# ST_LINK_V2.net
KiCad netlist of a schematic drawn in Altium Designer
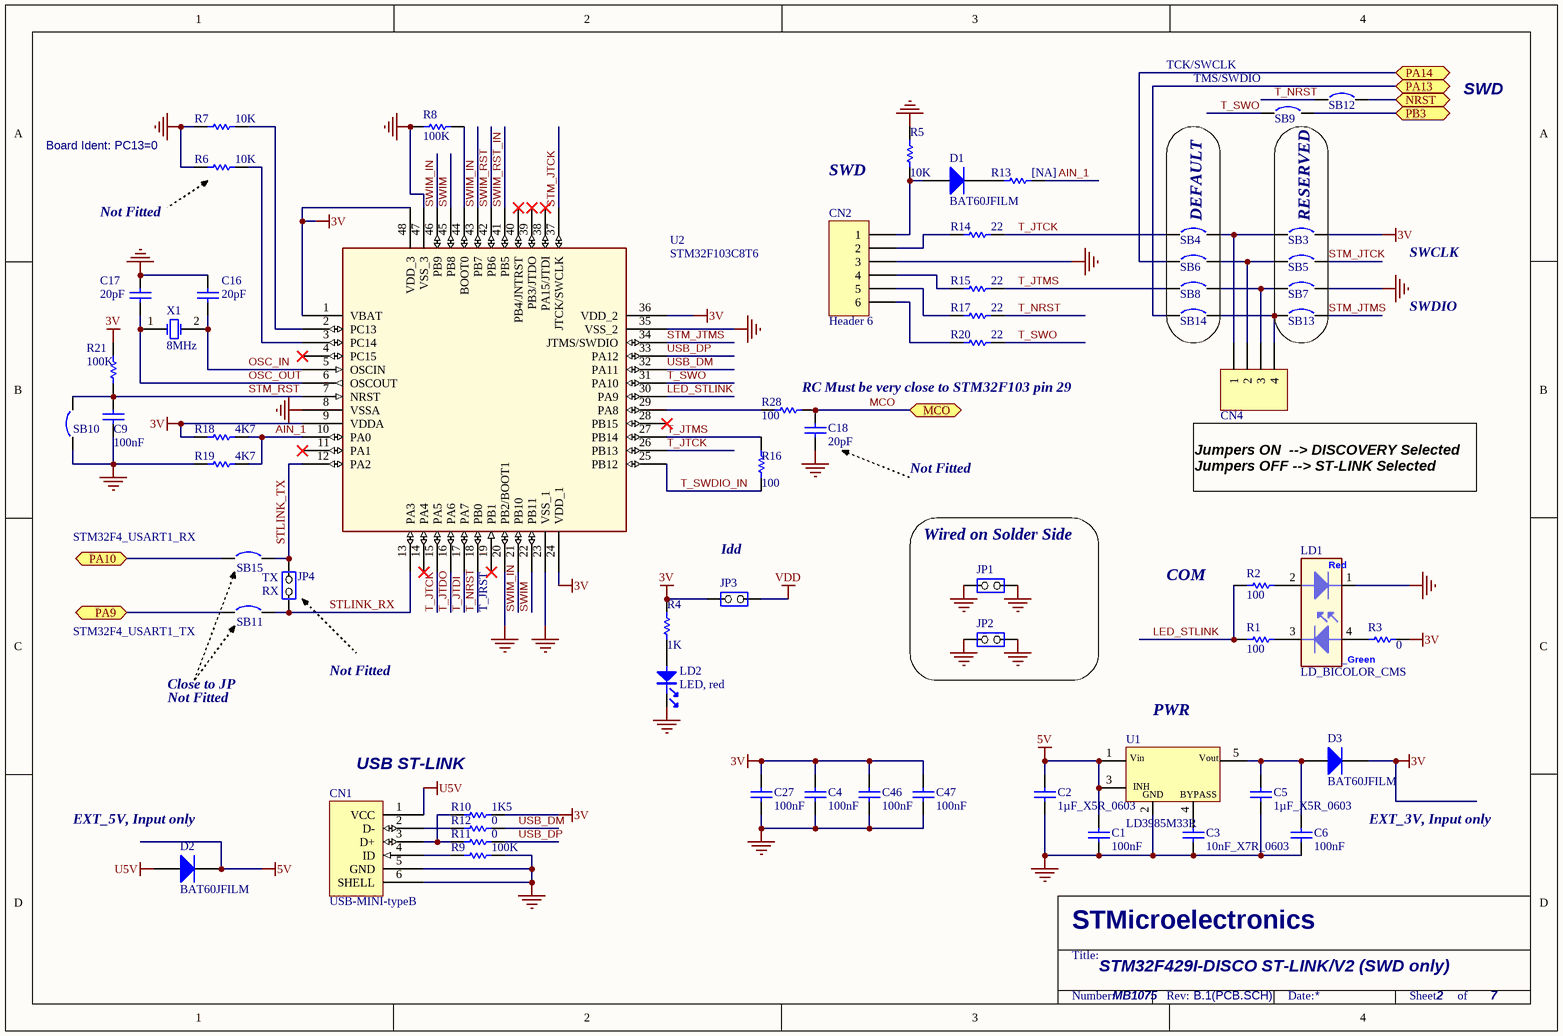
[diagram p0: ST_LINK_V2.SCHDOC]

(export (version "E")
  (design (tool "Eeschema 10.0.6"))
  (components
    (comp (ref "C1")
      (value "100nF")
      (footprint "0402C")
      (description "Capacitor 0402 / 0603 / 0805")
      (libsource (lib "MCD_TOOLS") (part "Capacitor_ST"))
    )
    (comp (ref "C2")
      (value "1µF_X5R_0603")
      (footprint "0603C")
      (description "0603  X5R 1µF")
      (fields (field (name "TOLERANCE") "10%"))
      (libsource (lib "MB963_1") (part "CAP SMD 0603  X5R 1µF 25V 10%"))
    )
    (comp (ref "C3")
      (value "10nF_X7R_0603")
      (footprint "0603C")
      (description "0603  X7R 10NF")
      (fields (field (name "TOLERANCE") "10%"))
      (libsource (lib "MB963_1") (part "CAP SMD 0603  X7R 10000PF 50V 10%"))
    )
    (comp (ref "C4")
      (value "100nF")
      (footprint "0402C")
      (description "Capacitor 0402 / 0603 / 0805")
      (libsource (lib "MCD_TOOLS") (part "Capacitor_ST"))
    )
    (comp (ref "C5")
      (value "1µF_X5R_0603")
      (footprint "0603C")
      (description "0603  X5R 1µF")
      (fields (field (name "TOLERANCE") "10%"))
      (libsource (lib "MB963_1") (part "CAP SMD 0603  X5R 1µF 25V 10%"))
    )
    (comp (ref "C6")
      (value "100nF")
      (footprint "0402C")
      (description "Capacitor 0402 / 0603 / 0805")
      (libsource (lib "MCD_TOOLS") (part "Capacitor_ST"))
    )
    (comp (ref "C9")
      (value "100nF")
      (footprint "0402C")
      (description "Capacitor 0402 / 0603 / 0805")
      (libsource (lib "MCD_TOOLS") (part "Capacitor_ST"))
    )
    (comp (ref "C16")
      (value "20pF")
      (footprint "0402C")
      (description "Capacitor 0402 / 0603 / 0805")
      (libsource (lib "MCD_TOOLS") (part "Capacitor_ST"))
    )
    (comp (ref "C17")
      (value "20pF")
      (footprint "0402C")
      (description "Capacitor 0402 / 0603 / 0805")
      (libsource (lib "MCD_TOOLS") (part "Capacitor_ST"))
    )
    (comp (ref "C18")
      (value "20pF")
      (footprint "0402C")
      (description "Capacitor 0402 / 0603 / 0805")
      (libsource (lib "MCD_TOOLS") (part "Capacitor_ST"))
    )
    (comp (ref "C27")
      (value "100nF")
      (footprint "0402C")
      (description "Capacitor 0402 / 0603 / 0805")
      (libsource (lib "MCD_TOOLS") (part "Capacitor_ST"))
    )
    (comp (ref "C46")
      (value "100nF")
      (footprint "0402C")
      (description "Capacitor 0402 / 0603 / 0805")
      (libsource (lib "MCD_TOOLS") (part "Capacitor_ST"))
    )
    (comp (ref "C47")
      (value "100nF")
      (footprint "0402C")
      (description "Capacitor 0402 / 0603 / 0805")
      (libsource (lib "MCD_TOOLS") (part "Capacitor_ST"))
    )
    (comp (ref "CN1")
      (value "USB-MINI-typeB")
      (footprint "STM-SMEE:USB-MINI-B-SMD")
      (description "USB,MINI-USB-5P/F, 5075BMR-05-M")
      (libsource (lib "MCD_TOOLS") (part "USB-MINI-typeB connector"))
    )
    (comp (ref "CN2")
      (value "Header 6")
      (footprint "HDR1X6")
      (description "Header, 6-Pin")
      (fields (field (name "PUBLISHER") "Altium Limited"))
      (libsource (lib "Miscellaneous Connectors") (part "Header 6"))
    )
    (comp (ref "CN4")
      (value "Header 4")
      (footprint "Header 4")
      (description "Header, 4-Pin")
      (fields (field (name "PUBLISHER") "Altium Limited"))
      (libsource (lib "MB963_1") (part "Header 4"))
    )
    (comp (ref "D1")
      (value "BAT60JFILM")
      (footprint "SOD323/A")
      (libsource (lib "MCD_TOOLS") (part "BAT60JFILM"))
    )
    (comp (ref "D2")
      (value "BAT60JFILM")
      (footprint "SOD323/A")
      (libsource (lib "MCD_TOOLS") (part "BAT60JFILM"))
    )
    (comp (ref "D3")
      (value "BAT60JFILM")
      (footprint "SOD323/A")
      (libsource (lib "MCD_TOOLS") (part "BAT60JFILM"))
    )
    (comp (ref "JP1") (value "~") (footprint "SIP2/2.54") (libsource (lib "*") (part "JP2")))
    (comp (ref "JP2") (value "~") (footprint "SIP2/2.54") (libsource (lib "*") (part "JP2")))
    (comp (ref "JP3") (value "~") (footprint "SIP2/2.54") (libsource (lib "*") (part "JP2")))
    (comp (ref "JP4") (value "JP2") (footprint "SIP2/2.54") (libsource (lib "MCD_TOOLS") (part "JP2")))
    (comp (ref "LD1")
      (value "LD_BICOLOR_CMS")
      (footprint "STM-SMEE:HSMF-A201")
      (description "Bicolor Led")
      (libsource (lib "MCD_TOOLS") (part "LD_BICOLOR_CMS"))
    )
    (comp (ref "LD2")
      (value "LED, red")
      (footprint "0603D")
      (description "LED,red,0603,19-213-R6C-AP1Q2B/3T,everlight")
      (libsource (lib "MCD_TOOLS") (part "LED_red"))
    )
    (comp (ref "R1")
      (value "100")
      (footprint "0402R")
      (description "Resistor 0402 or 0603 or 0805")
      (libsource (lib "MCD_TOOLS") (part "Resistor_ST"))
    )
    (comp (ref "R2")
      (value "100")
      (footprint "0402R")
      (description "Resistor 0402 or 0603 or 0805")
      (libsource (lib "MCD_TOOLS") (part "Resistor_ST"))
    )
    (comp (ref "R3")
      (value "0")
      (footprint "0402R")
      (description "Resistor 0402 or 0603 or 0805")
      (libsource (lib "MCD_TOOLS") (part "Resistor_ST"))
    )
    (comp (ref "R4")
      (value "1K")
      (footprint "0402R")
      (description "Resistor 0402 or 0603 or 0805")
      (libsource (lib "MCD_TOOLS") (part "Resistor_ST"))
    )
    (comp (ref "R5")
      (value "10K")
      (footprint "0402R")
      (description "Resistor 0402 or 0603 or 0805")
      (libsource (lib "MCD_TOOLS") (part "Resistor_ST"))
    )
    (comp (ref "R6")
      (value "10K")
      (footprint "0402R")
      (description "Resistor 0402 or 0603 or 0805")
      (libsource (lib "MCD_TOOLS") (part "Resistor_ST"))
    )
    (comp (ref "R7")
      (value "10K")
      (footprint "0402R")
      (description "Resistor 0402 or 0603 or 0805")
      (libsource (lib "MCD_TOOLS") (part "Resistor_ST"))
    )
    (comp (ref "R8")
      (value "100K")
      (footprint "0402R")
      (description "Resistor 0402 or 0603 or 0805")
      (libsource (lib "MCD_TOOLS") (part "Resistor_ST"))
    )
    (comp (ref "R9")
      (value "100K")
      (footprint "0402R")
      (description "Resistor 0402 or 0603 or 0805")
      (libsource (lib "MCD_TOOLS") (part "Resistor_ST"))
    )
    (comp (ref "R10")
      (value "1K5")
      (footprint "0402R")
      (description "Resistor 0402 or 0603 or 0805")
      (libsource (lib "MCD_TOOLS") (part "Resistor_ST"))
    )
    (comp (ref "R11")
      (value "0")
      (footprint "0402R")
      (description "Resistor 0402 or 0603 or 0805")
      (libsource (lib "MCD_TOOLS") (part "Resistor_ST"))
    )
    (comp (ref "R12")
      (value "0")
      (footprint "0402R")
      (description "Resistor 0402 or 0603 or 0805")
      (libsource (lib "MCD_TOOLS") (part "Resistor_ST"))
    )
    (comp (ref "R13")
      (value "[NA]")
      (footprint "0402R")
      (description "Resistor 0402 or 0603 or 0805")
      (libsource (lib "MCD_TOOLS") (part "Resistor_ST"))
    )
    (comp (ref "R14")
      (value "22")
      (footprint "0402R")
      (description "Resistor 0402 or 0603 or 0805")
      (libsource (lib "MCD_TOOLS") (part "Resistor_ST"))
    )
    (comp (ref "R15")
      (value "22")
      (footprint "0402R")
      (description "Resistor 0402 or 0603 or 0805")
      (libsource (lib "MCD_TOOLS") (part "Resistor_ST"))
    )
    (comp (ref "R16")
      (value "100")
      (footprint "0402R")
      (description "Resistor 0402 or 0603 or 0805")
      (libsource (lib "MCD_TOOLS") (part "Resistor_ST"))
    )
    (comp (ref "R17")
      (value "22")
      (footprint "0402R")
      (description "Resistor 0402 or 0603 or 0805")
      (libsource (lib "MCD_TOOLS") (part "Resistor_ST"))
    )
    (comp (ref "R18")
      (value "4K7")
      (footprint "0402R")
      (description "Resistor 0402 or 0603 or 0805")
      (libsource (lib "MCD_TOOLS") (part "Resistor_ST"))
    )
    (comp (ref "R19")
      (value "4K7")
      (footprint "0402R")
      (description "Resistor 0402 or 0603 or 0805")
      (libsource (lib "MCD_TOOLS") (part "Resistor_ST"))
    )
    (comp (ref "R20")
      (value "22")
      (footprint "0402R")
      (description "Resistor 0402 or 0603 or 0805")
      (libsource (lib "MCD_TOOLS") (part "Resistor_ST"))
    )
    (comp (ref "R21")
      (value "100K")
      (footprint "0402R")
      (description "Resistor 0402 or 0603 or 0805")
      (libsource (lib "MCD_TOOLS") (part "Resistor_ST"))
    )
    (comp (ref "R28")
      (value "100")
      (footprint "0402R")
      (description "Resistor 0402 or 0603 or 0805")
      (libsource (lib "MCD_TOOLS") (part "Resistor_ST"))
    )
    (comp (ref "SB3")
      (value "Circuit Breaker")
      (footprint "JP2_SMD")
      (fields (field (name "PUBLISHER") "Altium Limited"))
      (libsource (lib "MB915") (part "Circuit Breaker"))
    )
    (comp (ref "SB4")
      (value "Circuit Breaker")
      (footprint "JP2_SMD")
      (fields (field (name "PUBLISHER") "Altium Limited"))
      (libsource (lib "MB915") (part "Circuit Breaker"))
    )
    (comp (ref "SB5")
      (value "Circuit Breaker")
      (footprint "JP2_SMD")
      (fields (field (name "PUBLISHER") "Altium Limited"))
      (libsource (lib "MB915") (part "Circuit Breaker"))
    )
    (comp (ref "SB6")
      (value "Circuit Breaker")
      (footprint "JP2_SMD")
      (fields (field (name "PUBLISHER") "Altium Limited"))
      (libsource (lib "MB915") (part "Circuit Breaker"))
    )
    (comp (ref "SB7")
      (value "Circuit Breaker")
      (footprint "JP2_SMD")
      (fields (field (name "PUBLISHER") "Altium Limited"))
      (libsource (lib "MB915") (part "Circuit Breaker"))
    )
    (comp (ref "SB8")
      (value "Circuit Breaker")
      (footprint "JP2_SMD")
      (fields (field (name "PUBLISHER") "Altium Limited"))
      (libsource (lib "MB915") (part "Circuit Breaker"))
    )
    (comp (ref "SB9")
      (value "Circuit Breaker")
      (footprint "JP2_SMD")
      (fields (field (name "PUBLISHER") "Altium Limited"))
      (libsource (lib "MCD_TOOLS") (part "Circuit Breaker"))
    )
    (comp (ref "SB10")
      (value "Circuit Breaker")
      (footprint "JP2_SMD")
      (fields (field (name "PUBLISHER") "Altium Limited"))
      (libsource (lib "MB915") (part "Circuit Breaker"))
    )
    (comp (ref "SB11")
      (value "Circuit Breaker")
      (footprint "JP2_SMD")
      (fields (field (name "PUBLISHER") "Altium Limited"))
      (libsource (lib "MCD_TOOLS") (part "Circuit Breaker"))
    )
    (comp (ref "SB12")
      (value "Circuit Breaker")
      (footprint "JP2_SMD")
      (fields (field (name "PUBLISHER") "Altium Limited"))
      (libsource (lib "MB915") (part "Circuit Breaker"))
    )
    (comp (ref "SB13")
      (value "Circuit Breaker")
      (footprint "JP2_SMD")
      (fields (field (name "PUBLISHER") "Altium Limited"))
      (libsource (lib "MB915") (part "Circuit Breaker"))
    )
    (comp (ref "SB14")
      (value "Circuit Breaker")
      (footprint "JP2_SMD")
      (fields (field (name "PUBLISHER") "Altium Limited"))
      (libsource (lib "MB915") (part "Circuit Breaker"))
    )
    (comp (ref "SB15")
      (value "Circuit Breaker")
      (footprint "JP2_SMD")
      (fields (field (name "PUBLISHER") "Altium Limited"))
      (libsource (lib "MCD_TOOLS") (part "Circuit Breaker"))
    )
    (comp (ref "U1")
      (value "LD3985M33R")
      (footprint "STM-SMEE:SOT-23-5L")
      (description "Ultra low drop-low noise BiCMOS voltage, regulators low ESR capacitors compatible")
      (libsource (lib "MCD_TOOLS") (part "LD3985M33R"))
    )
    (comp (ref "U2")
      (value "STM32F103C8T6")
      (footprint "QFP48 7X7")
      (description "Medium-density performance line ARM-based 32-bit MCU with 64KB Flash")
      (libsource (lib "MCD_TOOLS") (part "STM32F103C8T6"))
    )
    (comp (ref "X1")
      (value "8MHz")
      (footprint "STM-SMEE:XTAL1")
      (description "Crystal Oscillator,8Mhz,20PF,20PPM,-10-70 degree,DIP,HC-49S")
      (libsource (lib "MCD_TOOLS") (part "XTAL"))
    )
  )
  (nets
    (net (code "1") (name "/AIN_1") (class "Default")
      (node (ref "R13") (pin "2") (pinfunction "2_2") (pintype "passive"))
      (node (ref "R18") (pin "2") (pinfunction "2_2") (pintype "passive"))
      (node (ref "R19") (pin "2") (pinfunction "2_2") (pintype "passive"))
      (node (ref "U2") (pin "10") (pinfunction "PA0_10") (pintype "bidirectional"))
    )
    (net (code "2") (name "/LED_STLINK") (class "Default")
      (node (ref "R1") (pin "1") (pinfunction "1_1") (pintype "passive"))
      (node (ref "R2") (pin "1") (pinfunction "1_1") (pintype "passive"))
      (node (ref "U2") (pin "30") (pinfunction "PA9_30") (pintype "bidirectional"))
    )
    (net (code "3") (name "/MCO") (class "Default")
      (node (ref "C18") (pin "2") (pinfunction "2_2") (pintype "passive"))
      (node (ref "R28") (pin "2") (pinfunction "2_2") (pintype "passive"))
    )
    (net (code "4") (name "/NRST") (class "Default")
      (node (ref "SB12") (pin "2") (pinfunction "2_2") (pintype "passive"))
    )
    (net (code "5") (name "/OSC_IN") (class "Default")
      (node (ref "C16") (pin "1") (pinfunction "1_1") (pintype "passive"))
      (node (ref "U2") (pin "5") (pinfunction "OSCIN_5") (pintype "input"))
      (node (ref "X1") (pin "2") (pinfunction "OSC2_2") (pintype "passive"))
    )
    (net (code "6") (name "/OSC_OUT") (class "Default")
      (node (ref "C17") (pin "1") (pinfunction "1_1") (pintype "passive"))
      (node (ref "U2") (pin "6") (pinfunction "OSCOUT_6") (pintype "output"))
      (node (ref "X1") (pin "1") (pinfunction "OSC1_1") (pintype "passive"))
    )
    (net (code "7") (name "/PA9") (class "Default")
      (node (ref "SB11") (pin "1") (pinfunction "1_1") (pintype "passive"))
    )
    (net (code "8") (name "/PA10") (class "Default")
      (node (ref "SB15") (pin "1") (pinfunction "1_1") (pintype "passive"))
    )
    (net (code "9") (name "/PA13") (class "Default")
      (node (ref "SB14") (pin "1") (pinfunction "1_1") (pintype "passive"))
    )
    (net (code "10") (name "/PA14") (class "Default")
      (node (ref "SB6") (pin "1") (pinfunction "1_1") (pintype "passive"))
    )
    (net (code "11") (name "/PB3") (class "Default")
      (node (ref "SB9") (pin "2") (pinfunction "2_2") (pintype "passive"))
    )
    (net (code "12") (name "/STLINK_RX") (class "Default")
      (node (ref "JP4") (pin "1") (pinfunction "COMMON_1") (pintype "passive"))
      (node (ref "SB11") (pin "2") (pinfunction "2_2") (pintype "passive"))
      (node (ref "U2") (pin "13") (pinfunction "PA3_13") (pintype "bidirectional"))
    )
    (net (code "13") (name "/STLINK_TX") (class "Default")
      (node (ref "JP4") (pin "2") (pinfunction "NO_2") (pintype "passive"))
      (node (ref "SB15") (pin "2") (pinfunction "2_2") (pintype "passive"))
      (node (ref "U2") (pin "12") (pinfunction "PA2_12") (pintype "bidirectional"))
    )
    (net (code "14") (name "/STM_JTCK") (class "Default")
      (node (ref "SB5") (pin "2") (pinfunction "2_2") (pintype "passive"))
      (node (ref "U2") (pin "37") (pinfunction "JTCK/SWCLK_37") (pintype "bidirectional"))
    )
    (net (code "15") (name "/STM_JTMS") (class "Default")
      (node (ref "SB13") (pin "2") (pinfunction "2_2") (pintype "passive"))
      (node (ref "U2") (pin "34") (pinfunction "JTMS/SWDIO_34") (pintype "bidirectional"))
    )
    (net (code "16") (name "/STM_RST") (class "Default")
      (node (ref "C9") (pin "2") (pinfunction "2_2") (pintype "passive"))
      (node (ref "R21") (pin "1") (pinfunction "1_1") (pintype "passive"))
      (node (ref "SB10") (pin "2") (pinfunction "2_2") (pintype "passive"))
      (node (ref "U2") (pin "7") (pinfunction "NRST_7") (pintype "input"))
    )
    (net (code "17") (name "/SWIM") (class "Default")
      (node (ref "U2") (pin "22") (pinfunction "PB11_22") (pintype "bidirectional"))
      (node (ref "U2") (pin "45") (pinfunction "PB8_45") (pintype "bidirectional"))
    )
    (net (code "18") (name "/SWIM_IN") (class "Default")
      (node (ref "U2") (pin "21") (pinfunction "PB10_21") (pintype "bidirectional"))
      (node (ref "U2") (pin "43") (pinfunction "PB7_43") (pintype "bidirectional"))
      (node (ref "U2") (pin "46") (pinfunction "PB9_46") (pintype "bidirectional"))
    )
    (net (code "19") (name "/SWIM_RST") (class "Default")
      (node (ref "U2") (pin "42") (pinfunction "PB6_42") (pintype "bidirectional"))
    )
    (net (code "20") (name "/SWIM_RST_IN") (class "Default")
      (node (ref "U2") (pin "41") (pinfunction "PB5_41") (pintype "bidirectional"))
    )
    (net (code "21") (name "/T_JTCK") (class "Default")
      (node (ref "R14") (pin "2") (pinfunction "2_2") (pintype "passive"))
      (node (ref "SB4") (pin "1") (pinfunction "1_1") (pintype "passive"))
      (node (ref "U2") (pin "15") (pinfunction "PA5_15") (pintype "bidirectional"))
      (node (ref "U2") (pin "26") (pinfunction "PB13_26") (pintype "bidirectional"))
    )
    (net (code "22") (name "/T_JTDI") (class "Default")
      (node (ref "U2") (pin "17") (pinfunction "PA7_17") (pintype "bidirectional"))
    )
    (net (code "23") (name "/T_JTDO") (class "Default")
      (node (ref "U2") (pin "16") (pinfunction "PA6_16") (pintype "bidirectional"))
    )
    (net (code "24") (name "/T_JTMS") (class "Default")
      (node (ref "R15") (pin "2") (pinfunction "2_2") (pintype "passive"))
      (node (ref "R16") (pin "2") (pinfunction "2_2") (pintype "passive"))
      (node (ref "SB8") (pin "1") (pinfunction "1_1") (pintype "passive"))
      (node (ref "U2") (pin "27") (pinfunction "PB14_27") (pintype "bidirectional"))
    )
    (net (code "25") (name "/T_NRST") (class "Default")
      (node (ref "R17") (pin "2") (pinfunction "2_2") (pintype "passive"))
      (node (ref "SB12") (pin "1") (pinfunction "1_1") (pintype "passive"))
      (node (ref "U2") (pin "18") (pinfunction "PB0_18") (pintype "bidirectional"))
    )
    (net (code "26") (name "/T_SWDIO_IN") (class "Default")
      (node (ref "R16") (pin "1") (pinfunction "1_1") (pintype "passive"))
      (node (ref "U2") (pin "25") (pinfunction "PB12_25") (pintype "bidirectional"))
    )
    (net (code "27") (name "/T_SWO") (class "Default")
      (node (ref "R20") (pin "2") (pinfunction "2_2") (pintype "passive"))
      (node (ref "SB9") (pin "1") (pinfunction "1_1") (pintype "passive"))
      (node (ref "U2") (pin "31") (pinfunction "PA10_31") (pintype "bidirectional"))
    )
    (net (code "28") (name "/USB_DM") (class "Default")
      (node (ref "R12") (pin "2") (pinfunction "2_2") (pintype "passive"))
      (node (ref "U2") (pin "32") (pinfunction "PA11_32") (pintype "bidirectional"))
    )
    (net (code "29") (name "/USB_DP") (class "Default")
      (node (ref "R11") (pin "2") (pinfunction "2_2") (pintype "passive"))
      (node (ref "U2") (pin "33") (pinfunction "PA12_33") (pintype "bidirectional"))
    )
    (net (code "30") (name "3V") (class "Default")
      (node (ref "C27") (pin "2") (pinfunction "2_2") (pintype "passive"))
      (node (ref "C4") (pin "2") (pinfunction "2_2") (pintype "passive"))
      (node (ref "C46") (pin "2") (pinfunction "2_2") (pintype "passive"))
      (node (ref "C47") (pin "2") (pinfunction "2_2") (pintype "passive"))
      (node (ref "D3") (pin "2") (pinfunction "K_2") (pintype "passive"))
      (node (ref "JP3") (pin "1") (pinfunction "COMMON_1") (pintype "passive"))
      (node (ref "R10") (pin "2") (pinfunction "2_2") (pintype "passive"))
      (node (ref "R18") (pin "1") (pinfunction "1_1") (pintype "passive"))
      (node (ref "R21") (pin "2") (pinfunction "2_2") (pintype "passive"))
      (node (ref "R3") (pin "2") (pinfunction "2_2") (pintype "passive"))
      (node (ref "R4") (pin "2") (pinfunction "2_2") (pintype "passive"))
      (node (ref "SB3") (pin "2") (pinfunction "2_2") (pintype "passive"))
      (node (ref "U2") (pin "1") (pinfunction "VBAT_1") (pintype "power_in"))
      (node (ref "U2") (pin "24") (pinfunction "VDD_1_24") (pintype "power_in"))
      (node (ref "U2") (pin "36") (pinfunction "VDD_2_36") (pintype "power_in"))
      (node (ref "U2") (pin "48") (pinfunction "VDD_3_48") (pintype "power_in"))
      (node (ref "U2") (pin "9") (pinfunction "VDDA_9") (pintype "power_in"))
    )
    (net (code "31") (name "5V") (class "Default")
      (node (ref "C1") (pin "2") (pinfunction "2_2") (pintype "passive"))
      (node (ref "C2") (pin "2") (pinfunction "2_2") (pintype "passive"))
      (node (ref "D2") (pin "2") (pinfunction "K_2") (pintype "passive"))
      (node (ref "U1") (pin "1") (pinfunction "Vin_1") (pintype "passive"))
      (node (ref "U1") (pin "3") (pinfunction "CE_3") (pintype "passive"))
    )
    (net (code "32") (name "GND") (class "Default")
      (node (ref "C1") (pin "1") (pinfunction "1_1") (pintype "passive"))
      (node (ref "C16") (pin "2") (pinfunction "2_2") (pintype "passive"))
      (node (ref "C17") (pin "2") (pinfunction "2_2") (pintype "passive"))
      (node (ref "C18") (pin "1") (pinfunction "1_1") (pintype "passive"))
      (node (ref "C2") (pin "1") (pinfunction "1_1") (pintype "passive"))
      (node (ref "C27") (pin "1") (pinfunction "1_1") (pintype "passive"))
      (node (ref "C3") (pin "1") (pinfunction "1_1") (pintype "passive"))
      (node (ref "C4") (pin "1") (pinfunction "1_1") (pintype "passive"))
      (node (ref "C46") (pin "1") (pinfunction "1_1") (pintype "passive"))
      (node (ref "C47") (pin "1") (pinfunction "1_1") (pintype "passive"))
      (node (ref "C5") (pin "2") (pinfunction "2_2") (pintype "passive"))
      (node (ref "C6") (pin "1") (pinfunction "1_1") (pintype "passive"))
      (node (ref "C9") (pin "1") (pinfunction "1_1") (pintype "passive"))
      (node (ref "CN1") (pin "5") (pinfunction "GND_5") (pintype "passive"))
      (node (ref "CN1") (pin "6") (pinfunction "SHELL_6") (pintype "passive"))
      (node (ref "CN2") (pin "3") (pinfunction "3_3") (pintype "passive"))
      (node (ref "JP1") (pin "1") (pinfunction "COMMON_1") (pintype "passive"))
      (node (ref "JP1") (pin "2") (pinfunction "NO_2") (pintype "passive"))
      (node (ref "JP2") (pin "1") (pinfunction "COMMON_1") (pintype "passive"))
      (node (ref "JP2") (pin "2") (pinfunction "NO_2") (pintype "passive"))
      (node (ref "LD1") (pin "1") (pinfunction "1_1") (pintype "passive"))
      (node (ref "LD2") (pin "2") (pintype "passive"))
      (node (ref "R19") (pin "1") (pinfunction "1_1") (pintype "passive"))
      (node (ref "R5") (pin "2") (pinfunction "2_2") (pintype "passive"))
      (node (ref "R6") (pin "1") (pinfunction "1_1") (pintype "passive"))
      (node (ref "R7") (pin "1") (pinfunction "1_1") (pintype "passive"))
      (node (ref "R8") (pin "1") (pinfunction "1_1") (pintype "passive"))
      (node (ref "R9") (pin "2") (pinfunction "2_2") (pintype "passive"))
      (node (ref "SB10") (pin "1") (pinfunction "1_1") (pintype "passive"))
      (node (ref "SB7") (pin "2") (pinfunction "2_2") (pintype "passive"))
      (node (ref "U1") (pin "2") (pinfunction "GND_2") (pintype "passive"))
      (node (ref "U2") (pin "20") (pinfunction "PB2/BOOT1_20") (pintype "bidirectional"))
      (node (ref "U2") (pin "23") (pinfunction "VSS_1_23") (pintype "power_in"))
      (node (ref "U2") (pin "35") (pinfunction "VSS_2_35") (pintype "power_in"))
      (node (ref "U2") (pin "47") (pinfunction "VSS_3_47") (pintype "power_in"))
      (node (ref "U2") (pin "8") (pinfunction "VSSA_8") (pintype "power_in"))
    )
    (net (code "33") (name "Net-(CN1-D+)") (class "Default")
      (node (ref "CN1") (pin "3") (pinfunction "D+_3") (pintype "bidirectional"))
      (node (ref "R10") (pin "1") (pinfunction "1_1") (pintype "passive"))
      (node (ref "R11") (pin "1") (pinfunction "1_1") (pintype "passive"))
    )
    (net (code "34") (name "Net-(CN1-D-)") (class "Default")
      (node (ref "CN1") (pin "2") (pinfunction "D-_2") (pintype "bidirectional"))
      (node (ref "R12") (pin "1") (pinfunction "1_1") (pintype "passive"))
    )
    (net (code "35") (name "Net-(CN1-ID)") (class "Default")
      (node (ref "CN1") (pin "4") (pinfunction "ID_4") (pintype "input"))
      (node (ref "R9") (pin "1") (pinfunction "1_1") (pintype "passive"))
    )
    (net (code "36") (name "Net-(CN2-Pad2)") (class "Default")
      (node (ref "CN2") (pin "2") (pinfunction "2_2") (pintype "passive"))
      (node (ref "R14") (pin "1") (pinfunction "1_1") (pintype "passive"))
    )
    (net (code "37") (name "Net-(CN2-Pad4)") (class "Default")
      (node (ref "CN2") (pin "4") (pinfunction "4_4") (pintype "passive"))
      (node (ref "R15") (pin "1") (pinfunction "1_1") (pintype "passive"))
    )
    (net (code "38") (name "Net-(CN2-Pad5)") (class "Default")
      (node (ref "CN2") (pin "5") (pinfunction "5_5") (pintype "passive"))
      (node (ref "R17") (pin "1") (pinfunction "1_1") (pintype "passive"))
    )
    (net (code "39") (name "Net-(CN2-Pad6)") (class "Default")
      (node (ref "CN2") (pin "6") (pinfunction "6_6") (pintype "passive"))
      (node (ref "R20") (pin "1") (pinfunction "1_1") (pintype "passive"))
    )
    (net (code "40") (name "Net-(CN4-Pad1)") (class "Default")
      (node (ref "CN4") (pin "1") (pinfunction "1_1") (pintype "passive"))
      (node (ref "SB3") (pin "1") (pinfunction "1_1") (pintype "passive"))
      (node (ref "SB4") (pin "2") (pinfunction "2_2") (pintype "passive"))
    )
    (net (code "41") (name "Net-(CN4-Pad2)") (class "Default")
      (node (ref "CN4") (pin "2") (pinfunction "2_2") (pintype "passive"))
      (node (ref "SB5") (pin "1") (pinfunction "1_1") (pintype "passive"))
      (node (ref "SB6") (pin "2") (pinfunction "2_2") (pintype "passive"))
    )
    (net (code "42") (name "Net-(CN4-Pad3)") (class "Default")
      (node (ref "CN4") (pin "3") (pinfunction "3_3") (pintype "passive"))
      (node (ref "SB7") (pin "1") (pinfunction "1_1") (pintype "passive"))
      (node (ref "SB8") (pin "2") (pinfunction "2_2") (pintype "passive"))
    )
    (net (code "43") (name "Net-(CN4-Pad4)") (class "Default")
      (node (ref "CN4") (pin "4") (pinfunction "4_4") (pintype "passive"))
      (node (ref "SB13") (pin "1") (pinfunction "1_1") (pintype "passive"))
      (node (ref "SB14") (pin "2") (pinfunction "2_2") (pintype "passive"))
    )
    (net (code "44") (name "Net-(D1-A)") (class "Default")
      (node (ref "CN2") (pin "1") (pinfunction "1_1") (pintype "passive"))
      (node (ref "D1") (pin "1") (pinfunction "A_1") (pintype "passive"))
      (node (ref "R5") (pin "1") (pinfunction "1_1") (pintype "passive"))
    )
    (net (code "45") (name "Net-(D1-K)") (class "Default")
      (node (ref "D1") (pin "2") (pinfunction "K_2") (pintype "passive"))
      (node (ref "R13") (pin "1") (pinfunction "1_1") (pintype "passive"))
    )
    (net (code "46") (name "Net-(D3-A)") (class "Default")
      (node (ref "C5") (pin "1") (pinfunction "1_1") (pintype "passive"))
      (node (ref "C6") (pin "2") (pinfunction "2_2") (pintype "passive"))
      (node (ref "D3") (pin "1") (pinfunction "A_1") (pintype "passive"))
      (node (ref "U1") (pin "5") (pinfunction "Vout_5") (pintype "passive"))
    )
    (net (code "47") (name "Net-(LD1-Pad2)") (class "Default")
      (node (ref "LD1") (pin "2") (pinfunction "2_2") (pintype "passive"))
      (node (ref "R2") (pin "2") (pinfunction "2_2") (pintype "passive"))
    )
    (net (code "48") (name "Net-(LD1-Pad3)") (class "Default")
      (node (ref "LD1") (pin "3") (pinfunction "3_3") (pintype "passive"))
      (node (ref "R1") (pin "2") (pinfunction "2_2") (pintype "passive"))
    )
    (net (code "49") (name "Net-(LD1-Pad4)") (class "Default")
      (node (ref "LD1") (pin "4") (pinfunction "4_4") (pintype "passive"))
      (node (ref "R3") (pin "1") (pinfunction "1_1") (pintype "passive"))
    )
    (net (code "50") (name "Net-(LD2-Pad1)") (class "Default")
      (node (ref "LD2") (pin "1") (pintype "passive"))
      (node (ref "R4") (pin "1") (pinfunction "1_1") (pintype "passive"))
    )
    (net (code "51") (name "Net-(U1-BYPASS)") (class "Default")
      (node (ref "C3") (pin "2") (pinfunction "2_2") (pintype "passive"))
      (node (ref "U1") (pin "4") (pinfunction "BYPASS_4") (pintype "passive"))
    )
    (net (code "52") (name "Net-(U2-BOOT0)") (class "Default")
      (node (ref "R8") (pin "2") (pinfunction "2_2") (pintype "passive"))
      (node (ref "U2") (pin "44") (pinfunction "BOOT0_44") (pintype "bidirectional"))
    )
    (net (code "53") (name "Net-(U2-PA8)") (class "Default")
      (node (ref "R28") (pin "1") (pinfunction "1_1") (pintype "passive"))
      (node (ref "U2") (pin "29") (pinfunction "PA8_29") (pintype "bidirectional"))
    )
    (net (code "54") (name "Net-(U2-PC13)") (class "Default")
      (node (ref "R7") (pin "2") (pinfunction "2_2") (pintype "passive"))
      (node (ref "U2") (pin "2") (pinfunction "PC13_2") (pintype "bidirectional"))
    )
    (net (code "55") (name "Net-(U2-PC14)") (class "Default")
      (node (ref "R6") (pin "2") (pinfunction "2_2") (pintype "passive"))
      (node (ref "U2") (pin "3") (pinfunction "PC14_3") (pintype "bidirectional"))
    )
    (net (code "56") (name "U5V") (class "Default")
      (node (ref "CN1") (pin "1") (pinfunction "VCC_1") (pintype "power_in"))
      (node (ref "D2") (pin "1") (pinfunction "A_1") (pintype "passive"))
    )
    (net (code "57") (name "VDD") (class "Default")
      (node (ref "JP3") (pin "2") (pinfunction "NO_2") (pintype "passive"))
    )
    (net (code "58") (name "unconnected-(U2-PA1-Pad11)") (class "Default")
      (node (ref "U2") (pin "11") (pinfunction "PA1_11") (pintype "bidirectional+no_connect"))
    )
    (net (code "59") (name "unconnected-(U2-PA4-Pad14)") (class "Default")
      (node (ref "U2") (pin "14") (pinfunction "PA4_14") (pintype "bidirectional+no_connect"))
    )
    (net (code "60") (name "unconnected-(U2-PA15{slash}JTDI-Pad38)") (class "Default")
      (node (ref "U2") (pin "38") (pinfunction "PA15/JTDI_38") (pintype "bidirectional+no_connect"))
    )
    (net (code "61") (name "unconnected-(U2-PB1-Pad19)") (class "Default")
      (node (ref "U2") (pin "19") (pinfunction "PB1_19") (pintype "input+no_connect"))
    )
    (net (code "62") (name "unconnected-(U2-PB3{slash}JTDO-Pad39)") (class "Default")
      (node (ref "U2") (pin "39") (pinfunction "PB3/JTDO_39") (pintype "bidirectional+no_connect"))
    )
    (net (code "63") (name "unconnected-(U2-PB4{slash}JNTRST-Pad40)") (class "Default")
      (node (ref "U2") (pin "40") (pinfunction "PB4/JNTRST_40") (pintype "bidirectional+no_connect"))
    )
    (net (code "64") (name "unconnected-(U2-PB15-Pad28)") (class "Default")
      (node (ref "U2") (pin "28") (pinfunction "PB15_28") (pintype "bidirectional+no_connect"))
    )
    (net (code "65") (name "unconnected-(U2-PC15-Pad4)") (class "Default")
      (node (ref "U2") (pin "4") (pinfunction "PC15_4") (pintype "bidirectional+no_connect"))
    )
  )
)
